# RoverWing-V1_3.net
KiCad netlist of a schematic drawn in EAGLE
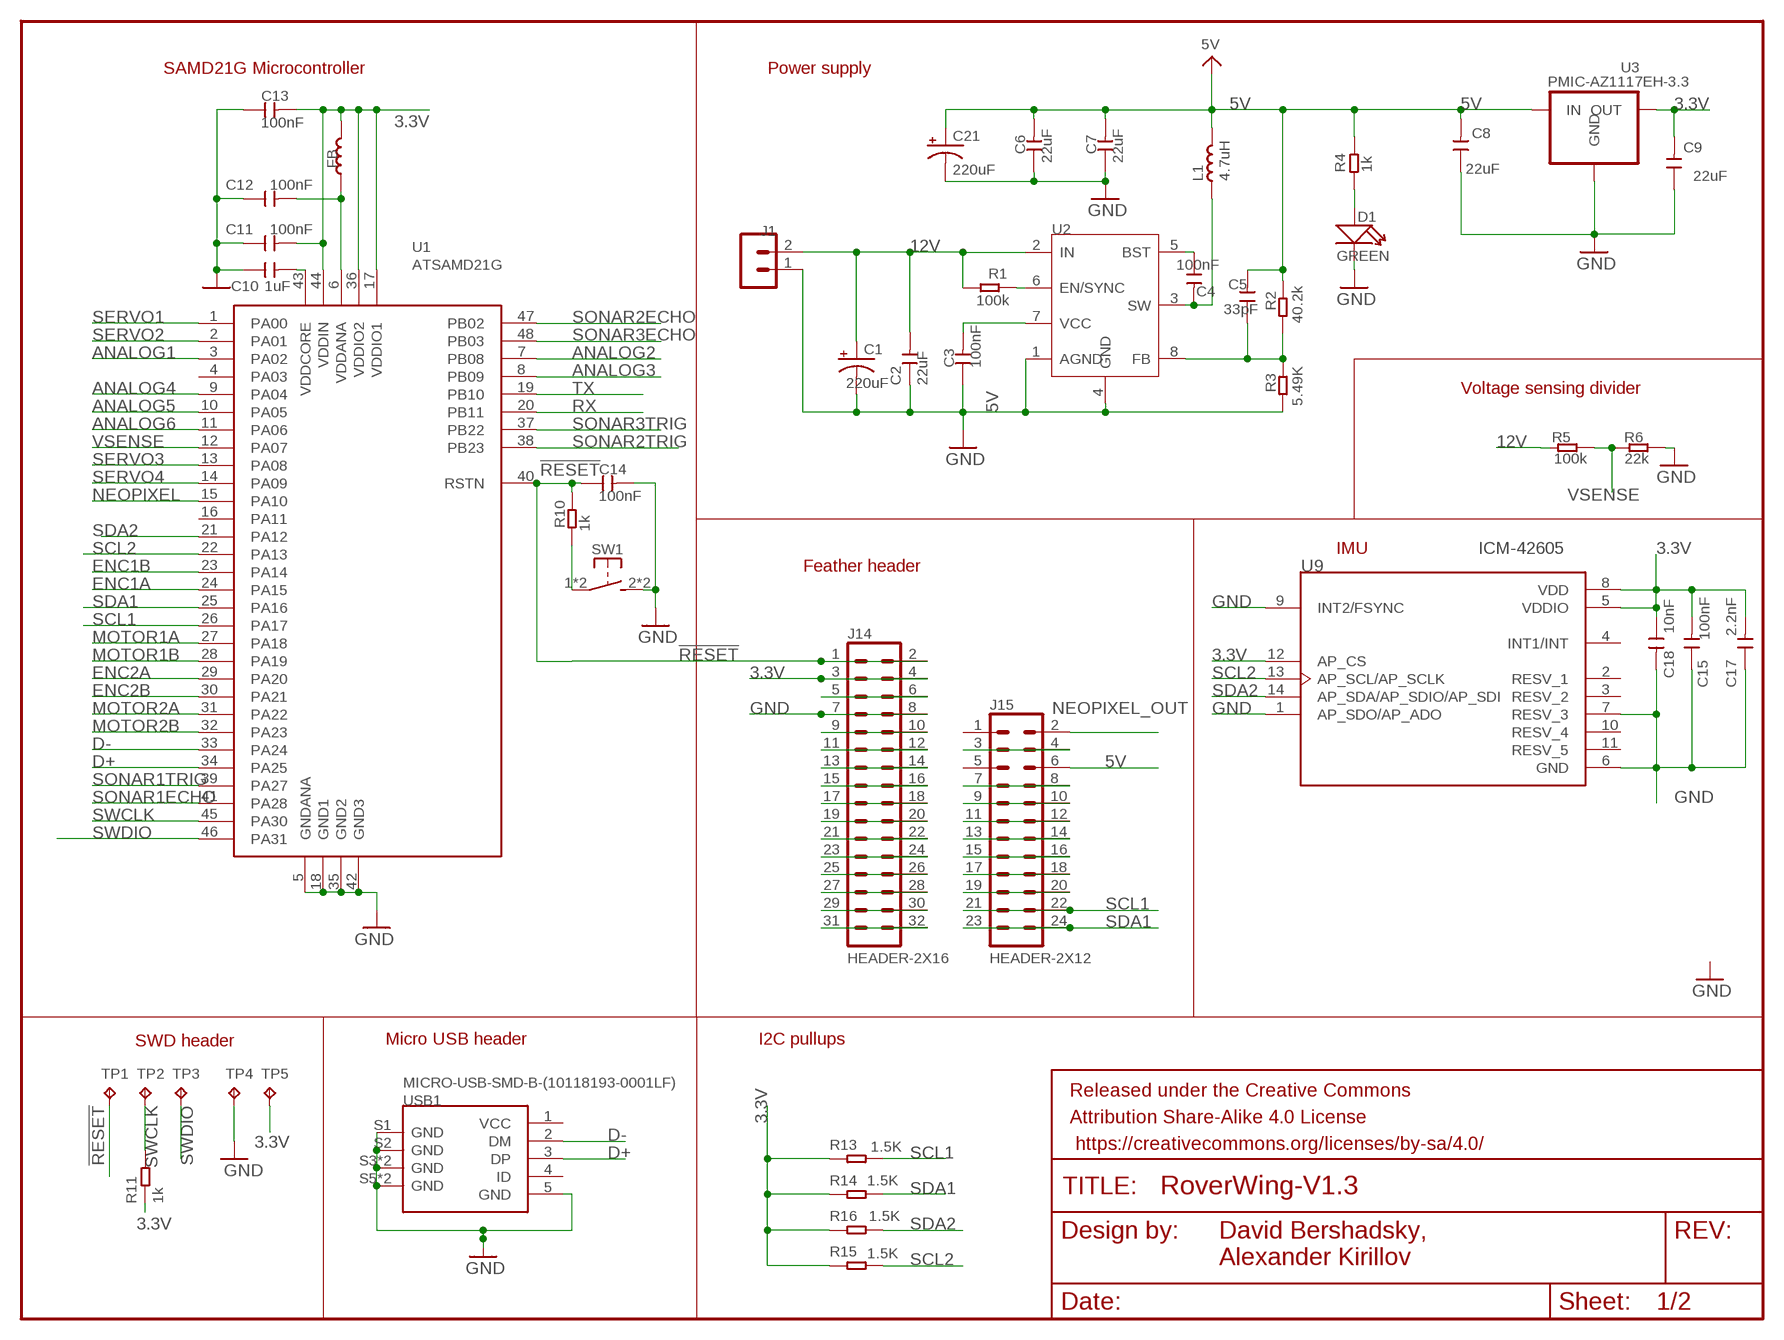
[diagram p0: schematic, sheet 1]
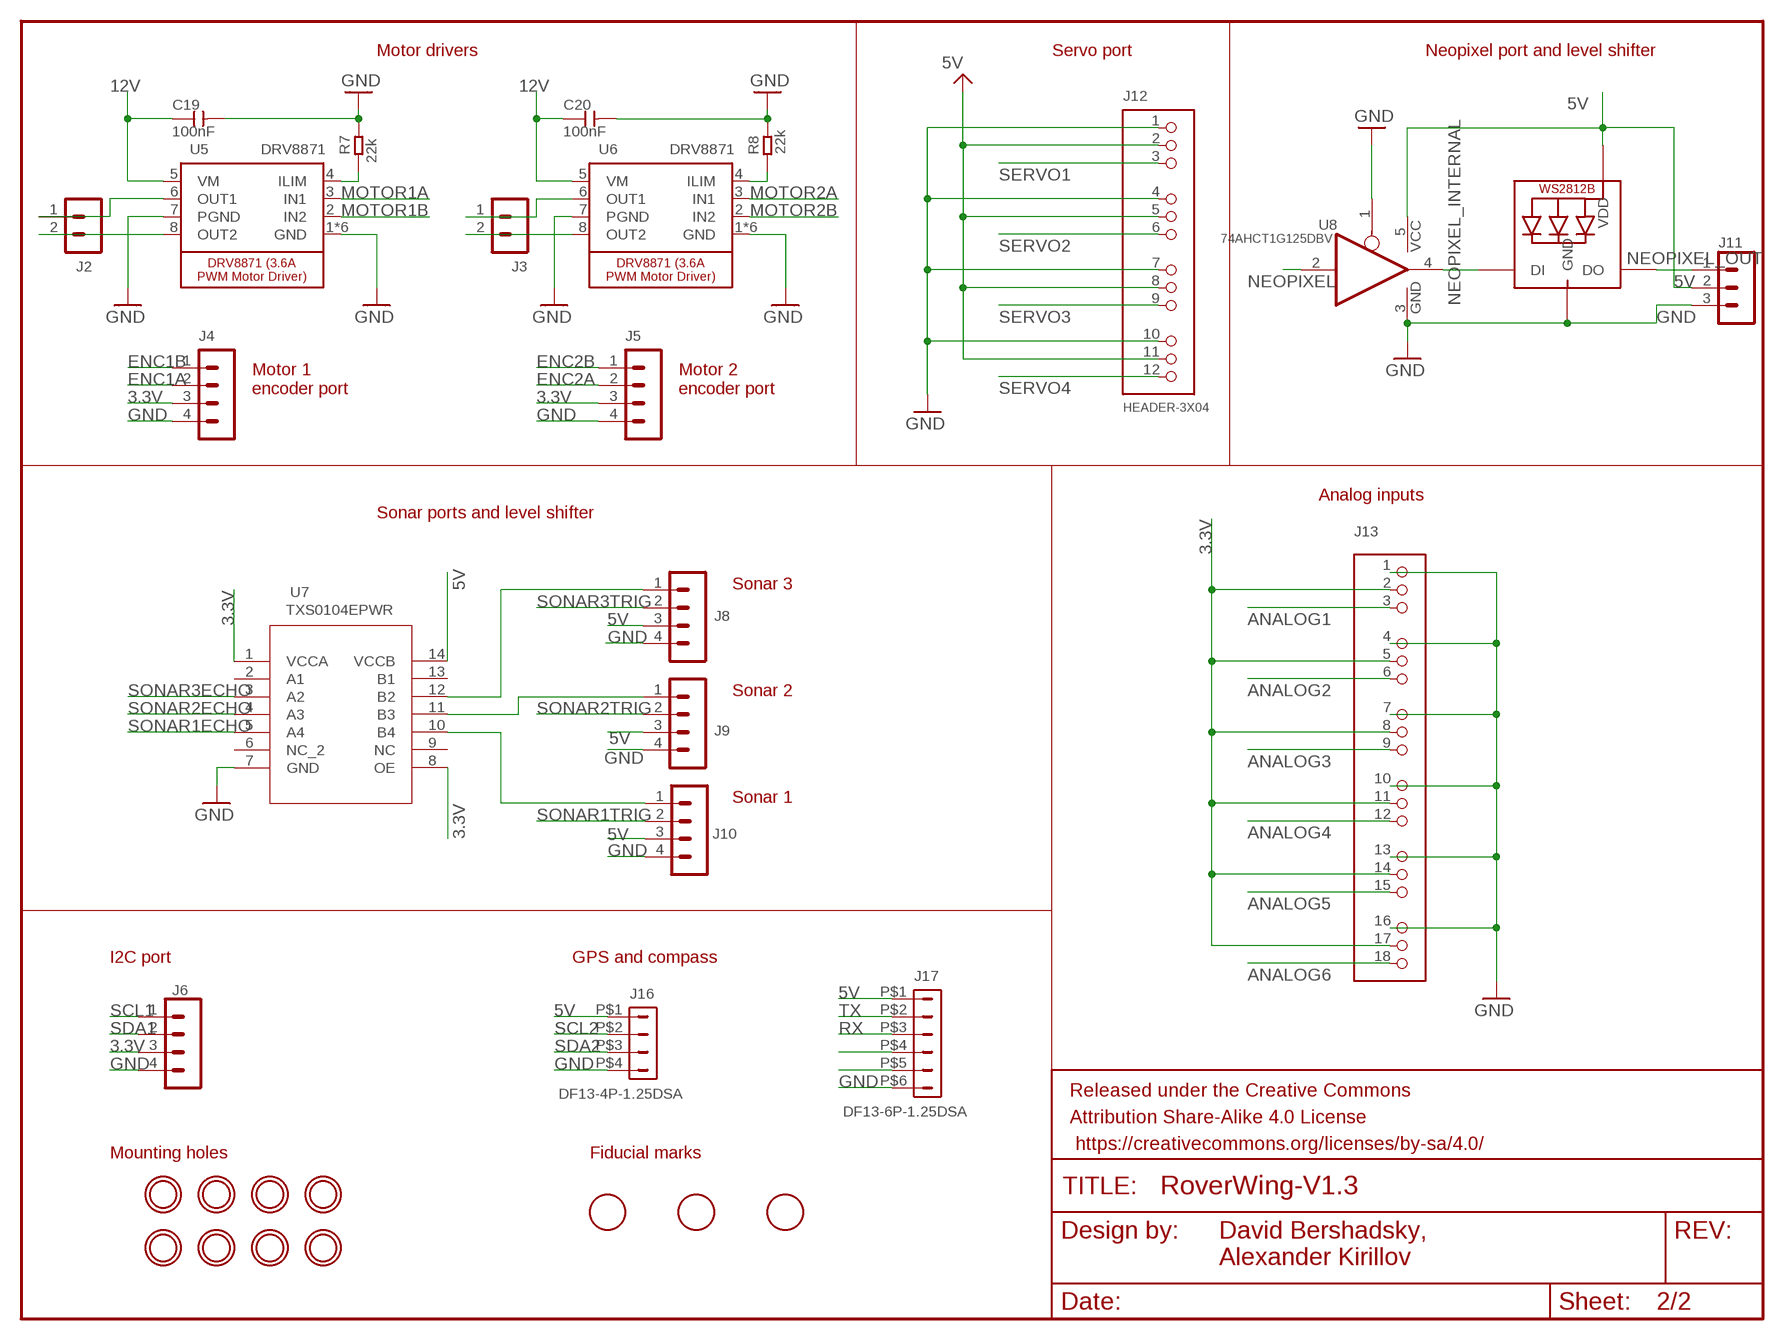
[diagram p1: schematic, sheet 2]

(export (version "E")
  (design (tool "Eeschema 10.0.6"))
  (components
    (comp (ref "C1")
      (value "220uF")
      (footprint "eagle-import:CAP-8X10.5")
      (libsource (lib "eagle-import") (part "CAP-POL-SMD-8X10.5"))
    )
    (comp (ref "C2")
      (value "22uF")
      (footprint "eagle-import:0805")
      (libsource (lib "eagle-import") (part "CAP-CERAMIC-SMD0805"))
    )
    (comp (ref "C3")
      (value "100nF")
      (footprint "eagle-import:0805")
      (libsource (lib "eagle-import") (part "CAP-CERAMIC-SMD0805"))
    )
    (comp (ref "C4")
      (value "100nF")
      (footprint "eagle-import:0805")
      (libsource (lib "eagle-import") (part "CAP-CERAMIC-SMD0805"))
    )
    (comp (ref "C5")
      (value "33pF")
      (footprint "eagle-import:0805")
      (libsource (lib "eagle-import") (part "CAP-CERAMIC-SMD0805"))
    )
    (comp (ref "C6")
      (value "22uF")
      (footprint "eagle-import:0805")
      (libsource (lib "eagle-import") (part "CAP-CERAMIC-SMD0805"))
    )
    (comp (ref "C7")
      (value "22uF")
      (footprint "eagle-import:0805")
      (libsource (lib "eagle-import") (part "CAP-CERAMIC-SMD0805"))
    )
    (comp (ref "C8")
      (value "22uF")
      (footprint "eagle-import:0805")
      (libsource (lib "eagle-import") (part "CAP-CERAMIC-SMD0805"))
    )
    (comp (ref "C9")
      (value "22uF")
      (footprint "eagle-import:0805")
      (libsource (lib "eagle-import") (part "CAP-CERAMIC-SMD0805"))
    )
    (comp (ref "C10")
      (value "1uF")
      (footprint "eagle-import:0805")
      (libsource (lib "eagle-import") (part "CAP-CERAMIC-SMD0805"))
    )
    (comp (ref "C11")
      (value "100nF")
      (footprint "eagle-import:0805")
      (libsource (lib "eagle-import") (part "CAP-CERAMIC-SMD0805"))
    )
    (comp (ref "C12")
      (value "100nF")
      (footprint "eagle-import:0805")
      (libsource (lib "eagle-import") (part "CAP-CERAMIC-SMD0805"))
    )
    (comp (ref "C13")
      (value "100nF")
      (footprint "eagle-import:0805")
      (libsource (lib "eagle-import") (part "CAP-CERAMIC-SMD0805"))
    )
    (comp (ref "C14")
      (value "100nF")
      (footprint "eagle-import:0805")
      (libsource (lib "eagle-import") (part "CAP-CERAMIC-SMD0805"))
    )
    (comp (ref "C15")
      (value "100nF")
      (footprint "eagle-import:0805")
      (libsource (lib "eagle-import") (part "CAP-CERAMIC-SMD0805"))
    )
    (comp (ref "C17")
      (value "2.2nF")
      (footprint "eagle-import:0805")
      (libsource (lib "eagle-import") (part "CAP-CERAMIC-SMD0805"))
    )
    (comp (ref "C18")
      (value "10nF")
      (footprint "eagle-import:0805")
      (libsource (lib "eagle-import") (part "CAP-CERAMIC-SMD0805"))
    )
    (comp (ref "C21")
      (value "220uF")
      (footprint "eagle-import:CAP-6.3X5.4")
      (fields (field (name "PARTNO") "CS1E470M-CRE54 "))
      (libsource (lib "eagle-import") (part "CAP-POL-SMD-6.3X5.4"))
    )
    (comp (ref "D1")
      (value "GREEN")
      (footprint "eagle-import:LED-0805")
      (libsource (lib "eagle-import") (part "SMD-LED-0805"))
    )
    (comp (ref "FB")
      (value "330R-1500MA")
      (footprint "eagle-import:0805")
      (fields (field (name "PARTNO") "BLM21PG331SN1D"))
      (libsource (lib "eagle-import") (part "SMD-FERRITE-BEAD-330R-1500MA(0805)"))
    )
    (comp (ref "FRAME2")
      (value "FRAME-LETTERNO_PACKAGE")
      (footprint "eagle-import:DUMMY")
      (libsource (lib "eagle-import") (part "FRAME-LETTERNO_PACKAGE"))
    )
    (comp (ref "J1")
      (value "HEADER-VH")
      (footprint "eagle-import:B2P-VH")
      (fields (field (name "PARTNO") "B2P-VH(LF)(SN)  "))
      (libsource (lib "eagle-import") (part "HEADER-VH"))
    )
    (comp (ref "J14")
      (value "HEADER-2X16")
      (footprint "eagle-import:2X16")
      (libsource (lib "eagle-import") (part "HEADER-2X16"))
    )
    (comp (ref "J15")
      (value "HEADER-2X12")
      (footprint "eagle-import:2X12")
      (libsource (lib "eagle-import") (part "HEADER-2X12"))
    )
    (comp (ref "L1")
      (value "4.7uH")
      (footprint "eagle-import:IND_TDK_7.1X6.5")
      (fields (field (name "MANUFACTURER") "TDK") (field (name "PARTNO") "SPM6530T-4R7M "))
      (libsource (lib "eagle-import") (part "IND-TDK-SPM6530T"))
    )
    (comp (ref "R1")
      (value "100k")
      (footprint "eagle-import:0805")
      (libsource (lib "eagle-import") (part "RES-SMD-0805"))
    )
    (comp (ref "R2")
      (value "40.2k")
      (footprint "eagle-import:0805")
      (libsource (lib "eagle-import") (part "RES-SMD-0805"))
    )
    (comp (ref "R3")
      (value "5.49K")
      (footprint "eagle-import:0805")
      (libsource (lib "eagle-import") (part "RES-SMD-0805"))
    )
    (comp (ref "R4")
      (value "1k")
      (footprint "eagle-import:0805")
      (libsource (lib "eagle-import") (part "RES-SMD-0805"))
    )
    (comp (ref "R5")
      (value "100k")
      (footprint "eagle-import:0805")
      (libsource (lib "eagle-import") (part "RES-SMD-0805"))
    )
    (comp (ref "R6")
      (value "22k")
      (footprint "eagle-import:0805")
      (libsource (lib "eagle-import") (part "RES-SMD-0805"))
    )
    (comp (ref "R10")
      (value "1k")
      (footprint "eagle-import:0805")
      (libsource (lib "eagle-import") (part "RES-SMD-0805"))
    )
    (comp (ref "R11")
      (value "1k")
      (footprint "eagle-import:0805")
      (libsource (lib "eagle-import") (part "RES-SMD-0805"))
    )
    (comp (ref "R13")
      (value "1.5K")
      (footprint "eagle-import:R0603")
      (fields (field (name "MPN") "RC0603FR-071K8L"))
      (libsource (lib "eagle-import") (part "SMD-RES-1.8K-1%-1/10W(0603)"))
    )
    (comp (ref "R14")
      (value "1.5K")
      (footprint "eagle-import:R0603")
      (fields (field (name "MPN") "RC0603FR-071K8L"))
      (libsource (lib "eagle-import") (part "SMD-RES-1.8K-1%-1/10W(0603)"))
    )
    (comp (ref "R15")
      (value "1.5K")
      (footprint "eagle-import:R0603")
      (fields (field (name "MPN") "RC0603FR-071K8L"))
      (libsource (lib "eagle-import") (part "SMD-RES-1.8K-1%-1/10W(0603)"))
    )
    (comp (ref "R16")
      (value "1.5K")
      (footprint "eagle-import:R0603")
      (fields (field (name "MPN") "RC0603FR-071K8L"))
      (libsource (lib "eagle-import") (part "SMD-RES-1.8K-1%-1/10W(0603)"))
    )
    (comp (ref "SW1")
      (value "SW-TACTILE-4.5X4.5_SMD")
      (footprint "eagle-import:TL3305")
      (fields (field (name "MANUFACTURER") "BRIGHT") (field (name "PARTNO") "TSA453G38-250 "))
      (libsource (lib "eagle-import") (part "SW-TACTILE-4.5X4.5_SMD"))
    )
    (comp (ref "TP1")
      (value "TPTP15R")
      (footprint "eagle-import:TP15R")
      (libsource (lib "eagle-import") (part "TPTP15R"))
    )
    (comp (ref "TP2")
      (value "TPTP15R")
      (footprint "eagle-import:TP15R")
      (libsource (lib "eagle-import") (part "TPTP15R"))
    )
    (comp (ref "TP3")
      (value "TPTP15R")
      (footprint "eagle-import:TP15R")
      (libsource (lib "eagle-import") (part "TPTP15R"))
    )
    (comp (ref "TP4")
      (value "TPTP15R")
      (footprint "eagle-import:TP15R")
      (libsource (lib "eagle-import") (part "TPTP15R"))
    )
    (comp (ref "TP5")
      (value "TPTP15R")
      (footprint "eagle-import:TP15R")
      (libsource (lib "eagle-import") (part "TPTP15R"))
    )
    (comp (ref "U1")
      (value "ATSAMD21G")
      (footprint "eagle-import:TQFP-48-EDITED")
      (fields (field (name "MANUFACTURER") "Microchip Technology") (field (name "PARTNO") "ATSAMD21G18A-AU"))
      (libsource (lib "eagle-import") (part "ATSAMD21G"))
    )
    (comp (ref "U2")
      (value "MP2225")
      (footprint "eagle-import:SOT-23-8")
      (fields (field (name "MANUFACTURER") "Monolithic Power Systems") (field (name "PARTNO") "MP2225GJ"))
      (libsource (lib "eagle-import") (part "PMIC-MP2225"))
    )
    (comp (ref "U3")
      (value "PMIC-AZ1117EH-3.3")
      (footprint "eagle-import:SOT223")
      (fields (field (name "PARTNO") "AZ1117EH-3.3TRG1"))
      (libsource (lib "eagle-import") (part "PMIC-AZ1117EH-3.3"))
    )
    (comp (ref "U9")
      (value "ICM-42605")
      (footprint "eagle-import:PQFN50P300X250X97-14N")
      (fields (field (name "DIGI-KEY_PART_NUMBER") "1428-1152-1-ND") (field (name "MF") "TDK InvenSense"))
      (libsource (lib "eagle-import") (part "ICM-42605"))
    )
    (comp (ref "USB1")
      (value "MICRO-USB-SMD-B-(10118193-0001LF)")
      (footprint "eagle-import:MICRO-USB5+6P-SMD-0.65-B")
      (fields (field (name "MANUFACTURER") "Amphenol ICC") (field (name "PARTNO") "10118193-0001LF"))
      (libsource (lib "eagle-import") (part "MICRO-USB-SMD-B-(10118193-0001LF)"))
    )
    (comp (ref "C19")
      (value "100nF")
      (footprint "eagle-import:0805")
      (libsource (lib "eagle-import") (part "CAP-CERAMIC-SMD0805"))
    )
    (comp (ref "C20")
      (value "100nF")
      (footprint "eagle-import:0805")
      (libsource (lib "eagle-import") (part "CAP-CERAMIC-SMD0805"))
    )
    (comp (ref "D2")
      (value "WS2812B3535")
      (footprint "eagle-import:LED3535")
      (fields (field (name "MANUFACTURER") "Worldsemi") (field (name "PARTNO") "WS2812B-3535 "))
      (libsource (lib "eagle-import") (part "WS2812B3535"))
    )
    (comp (ref "FRAME1")
      (value "FRAME-LETTERNO_PACKAGE")
      (footprint "eagle-import:DUMMY")
      (libsource (lib "eagle-import") (part "FRAME-LETTERNO_PACKAGE"))
    )
    (comp (ref "J2")
      (value "HEADER-VH")
      (footprint "eagle-import:B2P-VH")
      (fields (field (name "PARTNO") "B2P-VH(LF)(SN)  "))
      (libsource (lib "eagle-import") (part "HEADER-VH"))
    )
    (comp (ref "J3")
      (value "HEADER-VH")
      (footprint "eagle-import:B2P-VH")
      (fields (field (name "PARTNO") "B2P-VH(LF)(SN)  "))
      (libsource (lib "eagle-import") (part "HEADER-VH"))
    )
    (comp (ref "J4")
      (value "HEADER-PH-4P")
      (footprint "eagle-import:B4B-PH-K")
      (fields (field (name "PARTNO") "B4B-PH-K-S(LF)(SN)"))
      (libsource (lib "eagle-import") (part "HEADER-PH-4P"))
    )
    (comp (ref "J5")
      (value "HEADER-PH-4P")
      (footprint "eagle-import:B4B-PH-K")
      (fields (field (name "PARTNO") "B4B-PH-K-S(LF)(SN)"))
      (libsource (lib "eagle-import") (part "HEADER-PH-4P"))
    )
    (comp (ref "J6")
      (value "HEADER-PH-4P")
      (footprint "eagle-import:B4B-PH-K")
      (fields (field (name "PARTNO") "B4B-PH-K-S(LF)(SN)"))
      (libsource (lib "eagle-import") (part "HEADER-PH-4P"))
    )
    (comp (ref "J8")
      (value "HEADER-PH-4P")
      (footprint "eagle-import:B4B-PH-K")
      (fields (field (name "PARTNO") "B4B-PH-K-S(LF)(SN)"))
      (libsource (lib "eagle-import") (part "HEADER-PH-4P"))
    )
    (comp (ref "J9")
      (value "HEADER-PH-4P")
      (footprint "eagle-import:B4B-PH-K")
      (fields (field (name "PARTNO") "B4B-PH-K-S(LF)(SN)"))
      (libsource (lib "eagle-import") (part "HEADER-PH-4P"))
    )
    (comp (ref "J10")
      (value "HEADER-PH-4P")
      (footprint "eagle-import:B4B-PH-K")
      (fields (field (name "PARTNO") "B4B-PH-K-S(LF)(SN)"))
      (libsource (lib "eagle-import") (part "HEADER-PH-4P"))
    )
    (comp (ref "J11")
      (value "HEADER-PH-3P")
      (footprint "eagle-import:B3B-PH-K")
      (fields (field (name "PARTNO") "B3B-PH-K-S(LF)(SN)"))
      (libsource (lib "eagle-import") (part "HEADER-PH-3P"))
    )
    (comp (ref "J12")
      (value "HEADER-3X04")
      (footprint "eagle-import:3X04")
      (libsource (lib "eagle-import") (part "HEADER-3X04"))
    )
    (comp (ref "J13")
      (value "HEADER-3X06\"")
      (footprint "eagle-import:3X06")
      (libsource (lib "eagle-import") (part "HEADER-3X06{dblquote}"))
    )
    (comp (ref "J16")
      (value "DF13-4P-1.25DSA")
      (footprint "eagle-import:DF13-4P-1.25DSA")
      (libsource (lib "eagle-import") (part "DF13-4P-1.25DSA"))
    )
    (comp (ref "J17")
      (value "DF13-6P-1.25DSA")
      (footprint "eagle-import:DF13-6P-1.25DSA")
      (libsource (lib "eagle-import") (part "DF13-6P-1.25DSA"))
    )
    (comp (ref "R7")
      (value "22k")
      (footprint "eagle-import:0805")
      (libsource (lib "eagle-import") (part "RES-SMD-0805"))
    )
    (comp (ref "R8")
      (value "22k")
      (footprint "eagle-import:0805")
      (libsource (lib "eagle-import") (part "RES-SMD-0805"))
    )
    (comp (ref "U$3")
      (value "MOUNTINGHOLE3.0_NPH")
      (footprint "eagle-import:MOUNTINGHOLE_3.0_NPH")
      (libsource (lib "eagle-import") (part "MOUNTINGHOLE3.0_NPH"))
    )
    (comp (ref "U$4")
      (value "MOUNTINGHOLE3.0_NPH")
      (footprint "eagle-import:MOUNTINGHOLE_3.0_NPH")
      (libsource (lib "eagle-import") (part "MOUNTINGHOLE3.0_NPH"))
    )
    (comp (ref "U$11")
      (value "FIDUCIAL")
      (footprint "eagle-import:FIDUCIAL_1MM")
      (libsource (lib "eagle-import") (part "FIDUCIAL"))
    )
    (comp (ref "U$13")
      (value "FIDUCIAL")
      (footprint "eagle-import:FIDUCIAL_1MM")
      (libsource (lib "eagle-import") (part "FIDUCIAL"))
    )
    (comp (ref "U$14")
      (value "MOUNTINGHOLE3.0_NPH")
      (footprint "eagle-import:MOUNTINGHOLE_3.0_NPH")
      (libsource (lib "eagle-import") (part "MOUNTINGHOLE3.0_NPH"))
    )
    (comp (ref "U$15")
      (value "MOUNTINGHOLE3.0_NPH")
      (footprint "eagle-import:MOUNTINGHOLE_3.0_NPH")
      (libsource (lib "eagle-import") (part "MOUNTINGHOLE3.0_NPH"))
    )
    (comp (ref "U$17")
      (value "FIDUCIAL")
      (footprint "eagle-import:FIDUCIAL_1MM")
      (libsource (lib "eagle-import") (part "FIDUCIAL"))
    )
    (comp (ref "U$24")
      (value "MOUNTINGHOLE3.0_NPH")
      (footprint "eagle-import:MOUNTINGHOLE_3.0_NPH")
      (libsource (lib "eagle-import") (part "MOUNTINGHOLE3.0_NPH"))
    )
    (comp (ref "U$25")
      (value "MOUNTINGHOLE3.0_NPH")
      (footprint "eagle-import:MOUNTINGHOLE_3.0_NPH")
      (libsource (lib "eagle-import") (part "MOUNTINGHOLE3.0_NPH"))
    )
    (comp (ref "U$26")
      (value "MOUNTINGHOLE3.0_NPH")
      (footprint "eagle-import:MOUNTINGHOLE_3.0_NPH")
      (libsource (lib "eagle-import") (part "MOUNTINGHOLE3.0_NPH"))
    )
    (comp (ref "U$27")
      (value "MOUNTINGHOLE3.0_NPH")
      (footprint "eagle-import:MOUNTINGHOLE_3.0_NPH")
      (libsource (lib "eagle-import") (part "MOUNTINGHOLE3.0_NPH"))
    )
    (comp (ref "U5")
      (value "DRV8871")
      (footprint "eagle-import:HSOP8")
      (fields (field (name "MANUFACTURER") "TEXAS INSTRUMENTS") (field (name "PARTNO") "DRV8871DDAR"))
      (libsource (lib "eagle-import") (part "DRV8871"))
    )
    (comp (ref "U6")
      (value "DRV8871")
      (footprint "eagle-import:HSOP8")
      (fields (field (name "MANUFACTURER") "TEXAS INSTRUMENTS") (field (name "PARTNO") "DRV8871DDAR"))
      (libsource (lib "eagle-import") (part "DRV8871"))
    )
    (comp (ref "U7")
      (value "TXS0104EPWR")
      (footprint "eagle-import:PW14")
      (fields (field (name "MANUFACTURER") "Texas Instruments"))
      (libsource (lib "eagle-import") (part "TXS0104EPWR"))
    )
    (comp (ref "U8")
      (value "74AHCT1G125DBV")
      (footprint "eagle-import:SOT23-5")
      (fields (field (name "PARTNO") "SN74AHCT1G125DBVR"))
      (libsource (lib "eagle-import") (part "741G125DBVAHCT"))
    )
  )
  (nets
    (net (code "1") (name "3.3V") (class "Default")
      (node (ref "C11") (pin "2") (pinfunction "2_2") (pintype "passive"))
      (node (ref "C13") (pin "2") (pinfunction "2_2") (pintype "passive"))
      (node (ref "C15") (pin "2") (pinfunction "2_2") (pintype "passive"))
      (node (ref "C17") (pin "2") (pinfunction "2_2") (pintype "passive"))
      (node (ref "C18") (pin "1") (pinfunction "1_1") (pintype "passive"))
      (node (ref "C9") (pin "2") (pinfunction "2_2") (pintype "passive"))
      (node (ref "FB") (pin "2") (pinfunction "2_2") (pintype "passive"))
      (node (ref "J13") (pin "11") (pinfunction "11_11") (pintype "passive"))
      (node (ref "J13") (pin "14") (pinfunction "14_14") (pintype "passive"))
      (node (ref "J13") (pin "17") (pinfunction "17_17") (pintype "passive"))
      (node (ref "J13") (pin "2") (pinfunction "2_2") (pintype "passive"))
      (node (ref "J13") (pin "5") (pinfunction "5_5") (pintype "passive"))
      (node (ref "J13") (pin "8") (pinfunction "8_8") (pintype "passive"))
      (node (ref "J14") (pin "3") (pinfunction "3_3") (pintype "passive"))
      (node (ref "J14") (pin "4") (pinfunction "4_4") (pintype "passive"))
      (node (ref "J4") (pin "3") (pinfunction "3_3") (pintype "passive"))
      (node (ref "J5") (pin "3") (pinfunction "3_3") (pintype "passive"))
      (node (ref "J6") (pin "3") (pinfunction "3_3") (pintype "passive"))
      (node (ref "R11") (pin "1") (pinfunction "1_1") (pintype "passive"))
      (node (ref "R13") (pin "1") (pinfunction "1_1") (pintype "passive"))
      (node (ref "R14") (pin "1") (pinfunction "1_1") (pintype "passive"))
      (node (ref "R15") (pin "1") (pinfunction "1_1") (pintype "passive"))
      (node (ref "R16") (pin "1") (pinfunction "1_1") (pintype "passive"))
      (node (ref "TP5") (pin "TP") (pinfunction "TP_TP") (pintype "input"))
      (node (ref "U1") (pin "17") (pinfunction "VDDIO1_17") (pintype "power_in"))
      (node (ref "U1") (pin "36") (pinfunction "VDDIO2_36") (pintype "power_in"))
      (node (ref "U1") (pin "44") (pinfunction "VDDIN_44") (pintype "power_in"))
      (node (ref "U3") (pin "2") (pinfunction "OUT_2") (pintype "output"))
      (node (ref "U3") (pin "4") (pinfunction "OUT_4") (pintype "output"))
      (node (ref "U7") (pin "1") (pinfunction "VCCA_1") (pintype "power_in"))
      (node (ref "U7") (pin "8") (pinfunction "OE_8") (pintype "output"))
      (node (ref "U9") (pin "12") (pinfunction "AP_CS_12") (pintype "input"))
      (node (ref "U9") (pin "5") (pinfunction "VDDIO_5") (pintype "power_in"))
      (node (ref "U9") (pin "8") (pinfunction "VDD_8") (pintype "power_in"))
    )
    (net (code "2") (name "5V") (class "Default")
      (node (ref "C21") (pin "+") (pinfunction "+_+") (pintype "passive"))
      (node (ref "C5") (pin "2") (pinfunction "2_2") (pintype "passive"))
      (node (ref "C6") (pin "2") (pinfunction "2_2") (pintype "passive"))
      (node (ref "C7") (pin "2") (pinfunction "2_2") (pintype "passive"))
      (node (ref "C8") (pin "2") (pinfunction "2_2") (pintype "passive"))
      (node (ref "D2") (pin "3") (pinfunction "VDD_3") (pintype "power_in"))
      (node (ref "J10") (pin "3") (pinfunction "3_3") (pintype "passive"))
      (node (ref "J11") (pin "2") (pinfunction "2_2") (pintype "passive"))
      (node (ref "J12") (pin "11") (pinfunction "11_11") (pintype "passive"))
      (node (ref "J12") (pin "2") (pinfunction "2_2") (pintype "passive"))
      (node (ref "J12") (pin "5") (pinfunction "5_5") (pintype "passive"))
      (node (ref "J12") (pin "8") (pinfunction "8_8") (pintype "passive"))
      (node (ref "J15") (pin "6") (pinfunction "6_6") (pintype "passive"))
      (node (ref "J16") (pin "P$1") (pinfunction "1_P$1") (pintype "passive"))
      (node (ref "J17") (pin "P$1") (pinfunction "1_P$1") (pintype "passive"))
      (node (ref "J8") (pin "3") (pinfunction "3_3") (pintype "passive"))
      (node (ref "J9") (pin "3") (pinfunction "3_3") (pintype "passive"))
      (node (ref "L1") (pin "2") (pinfunction "2_2") (pintype "passive"))
      (node (ref "R2") (pin "1") (pinfunction "1_1") (pintype "passive"))
      (node (ref "R4") (pin "2") (pinfunction "2_2") (pintype "passive"))
      (node (ref "U3") (pin "3") (pinfunction "IN_3") (pintype "input"))
      (node (ref "U7") (pin "14") (pinfunction "VCCB_14") (pintype "power_in"))
      (node (ref "U8") (pin "5") (pinfunction "VCC_5") (pintype "power_in"))
    )
    (net (code "3") (name "12V") (class "Default")
      (node (ref "C1") (pin "+") (pinfunction "+_+") (pintype "passive"))
      (node (ref "C19") (pin "1") (pinfunction "1_1") (pintype "passive"))
      (node (ref "C2") (pin "2") (pinfunction "2_2") (pintype "passive"))
      (node (ref "C20") (pin "1") (pinfunction "1_1") (pintype "passive"))
      (node (ref "J1") (pin "2") (pinfunction "2_2") (pintype "passive"))
      (node (ref "R1") (pin "2") (pinfunction "2_2") (pintype "passive"))
      (node (ref "R5") (pin "2") (pinfunction "2_2") (pintype "passive"))
      (node (ref "U2") (pin "2") (pinfunction "IN_2") (pintype "bidirectional"))
      (node (ref "U5") (pin "5") (pinfunction "VM_5") (pintype "power_in"))
      (node (ref "U6") (pin "5") (pinfunction "VM_5") (pintype "power_in"))
    )
    (net (code "4") (name "ANALOG1") (class "Default")
      (node (ref "J13") (pin "3") (pinfunction "3_3") (pintype "passive"))
      (node (ref "U1") (pin "3") (pinfunction "PA02_3") (pintype "bidirectional"))
    )
    (net (code "5") (name "ANALOG2") (class "Default")
      (node (ref "J13") (pin "6") (pinfunction "6_6") (pintype "passive"))
      (node (ref "U1") (pin "7") (pinfunction "PB08_7") (pintype "bidirectional"))
    )
    (net (code "6") (name "ANALOG3") (class "Default")
      (node (ref "J13") (pin "9") (pinfunction "9_9") (pintype "passive"))
      (node (ref "U1") (pin "8") (pinfunction "PB09_8") (pintype "bidirectional"))
    )
    (net (code "7") (name "ANALOG4") (class "Default")
      (node (ref "J13") (pin "12") (pinfunction "12_12") (pintype "passive"))
      (node (ref "U1") (pin "9") (pinfunction "PA04_9") (pintype "bidirectional"))
    )
    (net (code "8") (name "ANALOG5") (class "Default")
      (node (ref "J13") (pin "15") (pinfunction "15_15") (pintype "passive"))
      (node (ref "U1") (pin "10") (pinfunction "PA05_10") (pintype "bidirectional"))
    )
    (net (code "9") (name "ANALOG6") (class "Default")
      (node (ref "J13") (pin "18") (pinfunction "18_18") (pintype "passive"))
      (node (ref "U1") (pin "11") (pinfunction "PA06_11") (pintype "bidirectional"))
    )
    (net (code "10") (name "D+") (class "Default")
      (node (ref "U1") (pin "34") (pinfunction "PA25_34") (pintype "bidirectional"))
      (node (ref "USB1") (pin "3") (pinfunction "DP_3") (pintype "bidirectional"))
    )
    (net (code "11") (name "D-") (class "Default")
      (node (ref "U1") (pin "33") (pinfunction "PA24_33") (pintype "bidirectional"))
      (node (ref "USB1") (pin "2") (pinfunction "DM_2") (pintype "bidirectional"))
    )
    (net (code "12") (name "ENC1A") (class "Default")
      (node (ref "J4") (pin "2") (pinfunction "2_2") (pintype "passive"))
      (node (ref "U1") (pin "24") (pinfunction "PA15_24") (pintype "bidirectional"))
    )
    (net (code "13") (name "ENC1B") (class "Default")
      (node (ref "J4") (pin "1") (pinfunction "1_1") (pintype "passive"))
      (node (ref "U1") (pin "23") (pinfunction "PA14_23") (pintype "bidirectional"))
    )
    (net (code "14") (name "ENC2A") (class "Default")
      (node (ref "J5") (pin "2") (pinfunction "2_2") (pintype "passive"))
      (node (ref "U1") (pin "29") (pinfunction "PA20_29") (pintype "bidirectional"))
    )
    (net (code "15") (name "ENC2B") (class "Default")
      (node (ref "J5") (pin "1") (pinfunction "1_1") (pintype "passive"))
      (node (ref "U1") (pin "30") (pinfunction "PA21_30") (pintype "bidirectional"))
    )
    (net (code "16") (name "GND") (class "Default")
      (node (ref "C1") (pin "-") (pinfunction "-_-") (pintype "passive"))
      (node (ref "C10") (pin "1") (pinfunction "1_1") (pintype "passive"))
      (node (ref "C11") (pin "1") (pinfunction "1_1") (pintype "passive"))
      (node (ref "C12") (pin "1") (pinfunction "1_1") (pintype "passive"))
      (node (ref "C13") (pin "1") (pinfunction "1_1") (pintype "passive"))
      (node (ref "C14") (pin "2") (pinfunction "2_2") (pintype "passive"))
      (node (ref "C15") (pin "1") (pinfunction "1_1") (pintype "passive"))
      (node (ref "C17") (pin "1") (pinfunction "1_1") (pintype "passive"))
      (node (ref "C18") (pin "2") (pinfunction "2_2") (pintype "passive"))
      (node (ref "C19") (pin "2") (pinfunction "2_2") (pintype "passive"))
      (node (ref "C2") (pin "1") (pinfunction "1_1") (pintype "passive"))
      (node (ref "C20") (pin "2") (pinfunction "2_2") (pintype "passive"))
      (node (ref "C21") (pin "-") (pinfunction "-_-") (pintype "passive"))
      (node (ref "C3") (pin "1") (pinfunction "1_1") (pintype "passive"))
      (node (ref "C6") (pin "1") (pinfunction "1_1") (pintype "passive"))
      (node (ref "C7") (pin "1") (pinfunction "1_1") (pintype "passive"))
      (node (ref "C8") (pin "1") (pinfunction "1_1") (pintype "passive"))
      (node (ref "C9") (pin "1") (pinfunction "1_1") (pintype "passive"))
      (node (ref "D1") (pin "-") (pinfunction "-_-") (pintype "passive"))
      (node (ref "D2") (pin "1") (pinfunction "GND_1") (pintype "power_in"))
      (node (ref "J1") (pin "1") (pinfunction "1_1") (pintype "passive"))
      (node (ref "J10") (pin "4") (pinfunction "4_4") (pintype "passive"))
      (node (ref "J11") (pin "3") (pinfunction "3_3") (pintype "passive"))
      (node (ref "J12") (pin "1") (pinfunction "1_1") (pintype "passive"))
      (node (ref "J12") (pin "10") (pinfunction "10_10") (pintype "passive"))
      (node (ref "J12") (pin "4") (pinfunction "4_4") (pintype "passive"))
      (node (ref "J12") (pin "7") (pinfunction "7_7") (pintype "passive"))
      (node (ref "J13") (pin "1") (pinfunction "1_1") (pintype "passive"))
      (node (ref "J13") (pin "10") (pinfunction "10_10") (pintype "passive"))
      (node (ref "J13") (pin "13") (pinfunction "13_13") (pintype "passive"))
      (node (ref "J13") (pin "16") (pinfunction "16_16") (pintype "passive"))
      (node (ref "J13") (pin "4") (pinfunction "4_4") (pintype "passive"))
      (node (ref "J13") (pin "7") (pinfunction "7_7") (pintype "passive"))
      (node (ref "J14") (pin "7") (pinfunction "7_7") (pintype "passive"))
      (node (ref "J14") (pin "8") (pinfunction "8_8") (pintype "passive"))
      (node (ref "J16") (pin "P$4") (pinfunction "4_P$4") (pintype "passive"))
      (node (ref "J17") (pin "P$6") (pinfunction "6_P$6") (pintype "passive"))
      (node (ref "J4") (pin "4") (pinfunction "4_4") (pintype "passive"))
      (node (ref "J5") (pin "4") (pinfunction "4_4") (pintype "passive"))
      (node (ref "J6") (pin "4") (pinfunction "4_4") (pintype "passive"))
      (node (ref "J8") (pin "4") (pinfunction "4_4") (pintype "passive"))
      (node (ref "J9") (pin "4") (pinfunction "4_4") (pintype "passive"))
      (node (ref "R3") (pin "2") (pinfunction "2_2") (pintype "passive"))
      (node (ref "R6") (pin "2") (pinfunction "2_2") (pintype "passive"))
      (node (ref "R7") (pin "2") (pinfunction "2_2") (pintype "passive"))
      (node (ref "R8") (pin "2") (pinfunction "2_2") (pintype "passive"))
      (node (ref "SW1") (pin "2") (pinfunction "S1_2") (pintype "passive"))
      (node (ref "SW1") (pin "3") (pinfunction "S1_3") (pintype "passive"))
      (node (ref "TP4") (pin "TP") (pinfunction "TP_TP") (pintype "input"))
      (node (ref "U1") (pin "18") (pinfunction "GND1_18") (pintype "power_in"))
      (node (ref "U1") (pin "35") (pinfunction "GND2_35") (pintype "power_in"))
      (node (ref "U1") (pin "42") (pinfunction "GND3_42") (pintype "power_in"))
      (node (ref "U1") (pin "5") (pinfunction "GNDANA_5") (pintype "power_in"))
      (node (ref "U2") (pin "1") (pinfunction "AGND_1") (pintype "bidirectional"))
      (node (ref "U2") (pin "4") (pinfunction "GND_4") (pintype "bidirectional"))
      (node (ref "U3") (pin "1") (pinfunction "GND_1") (pintype "power_in"))
      (node (ref "U5") (pin "1") (pinfunction "GND_1") (pintype "power_in"))
      (node (ref "U5") (pin "7") (pinfunction "PGND_7") (pintype "power_in"))
      (node (ref "U5") (pin "GND") (pinfunction "GND_GND") (pintype "power_in"))
      (node (ref "U5") (pin "P$1") (pinfunction "GND_P$1") (pintype "power_in"))
      (node (ref "U5") (pin "P$2") (pinfunction "GND_P$2") (pintype "power_in"))
      (node (ref "U5") (pin "P$3") (pinfunction "GND_P$3") (pintype "power_in"))
      (node (ref "U5") (pin "P$4") (pinfunction "GND_P$4") (pintype "power_in"))
      (node (ref "U6") (pin "1") (pinfunction "GND_1") (pintype "power_in"))
      (node (ref "U6") (pin "7") (pinfunction "PGND_7") (pintype "power_in"))
      (node (ref "U6") (pin "GND") (pinfunction "GND_GND") (pintype "power_in"))
      (node (ref "U6") (pin "P$1") (pinfunction "GND_P$1") (pintype "power_in"))
      (node (ref "U6") (pin "P$2") (pinfunction "GND_P$2") (pintype "power_in"))
      (node (ref "U6") (pin "P$3") (pinfunction "GND_P$3") (pintype "power_in"))
      (node (ref "U6") (pin "P$4") (pinfunction "GND_P$4") (pintype "power_in"))
      (node (ref "U7") (pin "7") (pinfunction "GND_7") (pintype "power_in"))
      (node (ref "U8") (pin "1") (pinfunction "OE_1") (pintype "input"))
      (node (ref "U8") (pin "3") (pinfunction "GND_3") (pintype "power_in"))
      (node (ref "U9") (pin "1") (pinfunction "AP_SDO/AP_ADO_1") (pintype "output"))
      (node (ref "U9") (pin "6") (pinfunction "GND_6") (pintype "power_in"))
      (node (ref "U9") (pin "7") (pinfunction "RESV_3_7") (pintype "bidirectional"))
      (node (ref "U9") (pin "9") (pinfunction "INT2/FSYNC_9") (pintype "bidirectional"))
      (node (ref "USB1") (pin "5") (pinfunction "GND_5") (pintype "bidirectional"))
      (node (ref "USB1") (pin "S1") (pinfunction "GND_S1") (pintype "bidirectional"))
      (node (ref "USB1") (pin "S2") (pinfunction "GND_S2") (pintype "bidirectional"))
      (node (ref "USB1") (pin "S3") (pinfunction "GND_S3") (pintype "bidirectional"))
      (node (ref "USB1") (pin "S4") (pinfunction "GND_S4") (pintype "bidirectional"))
      (node (ref "USB1") (pin "S5") (pinfunction "GND_S5") (pintype "bidirectional"))
      (node (ref "USB1") (pin "S6") (pinfunction "GND_S6") (pintype "bidirectional"))
    )
    (net (code "17") (name "MOTOR1A") (class "Default")
      (node (ref "U1") (pin "27") (pinfunction "PA18_27") (pintype "bidirectional"))
      (node (ref "U5") (pin "3") (pinfunction "IN1_3") (pintype "input"))
    )
    (net (code "18") (name "MOTOR1B") (class "Default")
      (node (ref "U1") (pin "28") (pinfunction "PA19_28") (pintype "bidirectional"))
      (node (ref "U5") (pin "2") (pinfunction "IN2_2") (pintype "input"))
    )
    (net (code "19") (name "MOTOR2A") (class "Default")
      (node (ref "U1") (pin "31") (pinfunction "PA22_31") (pintype "bidirectional"))
      (node (ref "U6") (pin "3") (pinfunction "IN1_3") (pintype "input"))
    )
    (net (code "20") (name "MOTOR2B") (class "Default")
      (node (ref "U1") (pin "32") (pinfunction "PA23_32") (pintype "bidirectional"))
      (node (ref "U6") (pin "2") (pinfunction "IN2_2") (pintype "input"))
    )
    (net (code "21") (name "NEOPIXEL") (class "Default")
      (node (ref "U1") (pin "15") (pinfunction "PA10_15") (pintype "bidirectional"))
      (node (ref "U8") (pin "2") (pinfunction "I_2") (pintype "input"))
    )
    (net (code "22") (name "NEOPIXEL_INTERNAL") (class "Default")
      (node (ref "D2") (pin "2") (pinfunction "DI_2") (pintype "input"))
      (node (ref "U8") (pin "4") (pinfunction "O_4") (pintype "tri_state"))
    )
    (net (code "23") (name "NEOPIXEL_OUT") (class "Default")
      (node (ref "D2") (pin "4") (pinfunction "DO_4") (pintype "output"))
      (node (ref "J11") (pin "1") (pinfunction "1_1") (pintype "passive"))
      (node (ref "J15") (pin "2") (pinfunction "2_2") (pintype "passive"))
    )
    (net (code "24") (name "Net-(D1-Pad+)") (class "Default")
      (node (ref "D1") (pin "+") (pinfunction "+_+") (pintype "passive"))
      (node (ref "R4") (pin "1") (pinfunction "1_1") (pintype "passive"))
    )
    (net (code "25") (name "Net-(J14-Pad5)") (class "Default")
      (node (ref "J14") (pin "5") (pinfunction "5_5") (pintype "passive"))
      (node (ref "J14") (pin "6") (pinfunction "6_6") (pintype "passive"))
    )
    (net (code "26") (name "Net-(J14-Pad10)") (class "Default")
      (node (ref "J14") (pin "10") (pinfunction "10_10") (pintype "passive"))
      (node (ref "J14") (pin "9") (pinfunction "9_9") (pintype "passive"))
    )
    (net (code "27") (name "Net-(J14-Pad11)") (class "Default")
      (node (ref "J14") (pin "11") (pinfunction "11_11") (pintype "passive"))
      (node (ref "J14") (pin "12") (pinfunction "12_12") (pintype "passive"))
    )
    (net (code "28") (name "Net-(J14-Pad13)") (class "Default")
      (node (ref "J14") (pin "13") (pinfunction "13_13") (pintype "passive"))
      (node (ref "J14") (pin "14") (pinfunction "14_14") (pintype "passive"))
    )
    (net (code "29") (name "Net-(J14-Pad15)") (class "Default")
      (node (ref "J14") (pin "15") (pinfunction "15_15") (pintype "passive"))
      (node (ref "J14") (pin "16") (pinfunction "16_16") (pintype "passive"))
    )
    (net (code "30") (name "Net-(J14-Pad17)") (class "Default")
      (node (ref "J14") (pin "17") (pinfunction "17_17") (pintype "passive"))
      (node (ref "J14") (pin "18") (pinfunction "18_18") (pintype "passive"))
    )
    (net (code "31") (name "Net-(J14-Pad19)") (class "Default")
      (node (ref "J14") (pin "19") (pinfunction "19_19") (pintype "passive"))
      (node (ref "J14") (pin "20") (pinfunction "20_20") (pintype "passive"))
    )
    (net (code "32") (name "Net-(J14-Pad21)") (class "Default")
      (node (ref "J14") (pin "21") (pinfunction "21_21") (pintype "passive"))
      (node (ref "J14") (pin "22") (pinfunction "22_22") (pintype "passive"))
    )
    (net (code "33") (name "Net-(J14-Pad23)") (class "Default")
      (node (ref "J14") (pin "23") (pinfunction "23_23") (pintype "passive"))
      (node (ref "J14") (pin "24") (pinfunction "24_24") (pintype "passive"))
    )
    (net (code "34") (name "Net-(J14-Pad25)") (class "Default")
      (node (ref "J14") (pin "25") (pinfunction "25_25") (pintype "passive"))
      (node (ref "J14") (pin "26") (pinfunction "26_26") (pintype "passive"))
    )
    (net (code "35") (name "Net-(J14-Pad27)") (class "Default")
      (node (ref "J14") (pin "27") (pinfunction "27_27") (pintype "passive"))
      (node (ref "J14") (pin "28") (pinfunction "28_28") (pintype "passive"))
    )
    (net (code "36") (name "Net-(J14-Pad29)") (class "Default")
      (node (ref "J14") (pin "29") (pinfunction "29_29") (pintype "passive"))
      (node (ref "J14") (pin "30") (pinfunction "30_30") (pintype "passive"))
    )
    (net (code "37") (name "Net-(J14-Pad31)") (class "Default")
      (node (ref "J14") (pin "31") (pinfunction "31_31") (pintype "passive"))
      (node (ref "J14") (pin "32") (pinfunction "32_32") (pintype "passive"))
    )
    (net (code "38") (name "Net-(J15-Pad3)") (class "Default")
      (node (ref "J15") (pin "3") (pinfunction "3_3") (pintype "passive"))
      (node (ref "J15") (pin "4") (pinfunction "4_4") (pintype "passive"))
    )
    (net (code "39") (name "Net-(J15-Pad7)") (class "Default")
      (node (ref "J15") (pin "7") (pinfunction "7_7") (pintype "passive"))
      (node (ref "J15") (pin "8") (pinfunction "8_8") (pintype "passive"))
    )
    (net (code "40") (name "Net-(J15-Pad10)") (class "Default")
      (node (ref "J15") (pin "10") (pinfunction "10_10") (pintype "passive"))
      (node (ref "J15") (pin "9") (pinfunction "9_9") (pintype "passive"))
    )
    (net (code "41") (name "Net-(J15-Pad11)") (class "Default")
      (node (ref "J15") (pin "11") (pinfunction "11_11") (pintype "passive"))
      (node (ref "J15") (pin "12") (pinfunction "12_12") (pintype "passive"))
    )
    (net (code "42") (name "Net-(J15-Pad13)") (class "Default")
      (node (ref "J15") (pin "13") (pinfunction "13_13") (pintype "passive"))
      (node (ref "J15") (pin "14") (pinfunction "14_14") (pintype "passive"))
    )
    (net (code "43") (name "Net-(J15-Pad15)") (class "Default")
      (node (ref "J15") (pin "15") (pinfunction "15_15") (pintype "passive"))
      (node (ref "J15") (pin "16") (pinfunction "16_16") (pintype "passive"))
    )
    (net (code "44") (name "Net-(J15-Pad17)") (class "Default")
      (node (ref "J15") (pin "17") (pinfunction "17_17") (pintype "passive"))
      (node (ref "J15") (pin "18") (pinfunction "18_18") (pintype "passive"))
    )
    (net (code "45") (name "Net-(J15-Pad19)") (class "Default")
      (node (ref "J15") (pin "19") (pinfunction "19_19") (pintype "passive"))
      (node (ref "J15") (pin "20") (pinfunction "20_20") (pintype "passive"))
    )
    (net (code "46") (name "Net-(R10-Pad1)") (class "Default")
      (node (ref "R10") (pin "1") (pinfunction "1_1") (pintype "passive"))
      (node (ref "SW1") (pin "1") (pinfunction "P1_1") (pintype "passive"))
      (node (ref "SW1") (pin "4") (pinfunction "P1_4") (pintype "passive"))
    )
    (net (code "47") (name "Net-(U1-VDDANA)") (class "Default")
      (node (ref "C12") (pin "2") (pinfunction "2_2") (pintype "passive"))
      (node (ref "FB") (pin "1") (pinfunction "1_1") (pintype "passive"))
      (node (ref "U1") (pin "6") (pinfunction "VDDANA_6") (pintype "power_in"))
    )
    (net (code "48") (name "Net-(U1-VDDCORE)") (class "Default")
      (node (ref "C10") (pin "2") (pinfunction "2_2") (pintype "passive"))
      (node (ref "U1") (pin "43") (pinfunction "VDDCORE_43") (pintype "power_in"))
    )
    (net (code "49") (name "Net-(U2-BST)") (class "Default")
      (node (ref "C4") (pin "1") (pinfunction "1_1") (pintype "passive"))
      (node (ref "U2") (pin "5") (pinfunction "BST_5") (pintype "bidirectional"))
    )
    (net (code "50") (name "Net-(U2-EN{slash}SYNC)") (class "Default")
      (node (ref "R1") (pin "1") (pinfunction "1_1") (pintype "passive"))
      (node (ref "U2") (pin "6") (pinfunction "EN/SYNC_6") (pintype "bidirectional"))
    )
    (net (code "51") (name "Net-(U2-FB)") (class "Default")
      (node (ref "C5") (pin "1") (pinfunction "1_1") (pintype "passive"))
      (node (ref "R2") (pin "2") (pinfunction "2_2") (pintype "passive"))
      (node (ref "R3") (pin "1") (pinfunction "1_1") (pintype "passive"))
      (node (ref "U2") (pin "8") (pinfunction "FB_8") (pintype "bidirectional"))
    )
    (net (code "52") (name "Net-(U2-SW)") (class "Default")
      (node (ref "C4") (pin "2") (pinfunction "2_2") (pintype "passive"))
      (node (ref "L1") (pin "1") (pinfunction "1_1") (pintype "passive"))
      (node (ref "U2") (pin "3") (pinfunction "SW_3") (pintype "bidirectional"))
    )
    (net (code "53") (name "Net-(U2-VCC)") (class "Default")
      (node (ref "C3") (pin "2") (pinfunction "2_2") (pintype "passive"))
      (node (ref "U2") (pin "7") (pinfunction "VCC_7") (pintype "bidirectional"))
    )
    (net (code "54") (name "Net-(U5-ILIM)") (class "Default")
      (node (ref "R7") (pin "1") (pinfunction "1_1") (pintype "passive"))
      (node (ref "U5") (pin "4") (pinfunction "ILIM_4") (pintype "input"))
    )
    (net (code "55") (name "Net-(U5-OUT1)") (class "Default")
      (node (ref "J2") (pin "1") (pinfunction "1_1") (pintype "passive"))
      (node (ref "U5") (pin "6") (pinfunction "OUT1_6") (pintype "output"))
    )
    (net (code "56") (name "Net-(U5-OUT2)") (class "Default")
      (node (ref "J2") (pin "2") (pinfunction "2_2") (pintype "passive"))
      (node (ref "U5") (pin "8") (pinfunction "OUT2_8") (pintype "output"))
    )
    (net (code "57") (name "Net-(U6-ILIM)") (class "Default")
      (node (ref "R8") (pin "1") (pinfunction "1_1") (pintype "passive"))
      (node (ref "U6") (pin "4") (pinfunction "ILIM_4") (pintype "input"))
    )
    (net (code "58") (name "Net-(U6-OUT1)") (class "Default")
      (node (ref "J3") (pin "1") (pinfunction "1_1") (pintype "passive"))
      (node (ref "U6") (pin "6") (pinfunction "OUT1_6") (pintype "output"))
    )
    (net (code "59") (name "Net-(U6-OUT2)") (class "Default")
      (node (ref "J3") (pin "2") (pinfunction "2_2") (pintype "passive"))
      (node (ref "U6") (pin "8") (pinfunction "OUT2_8") (pintype "output"))
    )
    (net (code "60") (name "Net-(U7-B2)") (class "Default")
      (node (ref "J8") (pin "1") (pinfunction "1_1") (pintype "passive"))
      (node (ref "U7") (pin "12") (pinfunction "B2_12") (pintype "bidirectional"))
    )
    (net (code "61") (name "Net-(U7-B3)") (class "Default")
      (node (ref "J9") (pin "1") (pinfunction "1_1") (pintype "passive"))
      (node (ref "U7") (pin "11") (pinfunction "B3_11") (pintype "bidirectional"))
    )
    (net (code "62") (name "Net-(U7-B4)") (class "Default")
      (node (ref "J10") (pin "1") (pinfunction "1_1") (pintype "passive"))
      (node (ref "U7") (pin "10") (pinfunction "B4_10") (pintype "bidirectional"))
    )
    (net (code "63") (name "RX") (class "Default")
      (node (ref "J17") (pin "P$3") (pinfunction "3_P$3") (pintype "passive"))
      (node (ref "U1") (pin "20") (pinfunction "PB11_20") (pintype "bidirectional"))
    )
    (net (code "64") (name "SCL1") (class "Default")
      (node (ref "J15") (pin "21") (pinfunction "21_21") (pintype "passive"))
      (node (ref "J15") (pin "22") (pinfunction "22_22") (pintype "passive"))
      (node (ref "J6") (pin "1") (pinfunction "1_1") (pintype "passive"))
      (node (ref "R13") (pin "2") (pinfunction "2_2") (pintype "passive"))
      (node (ref "U1") (pin "26") (pinfunction "PA17_26") (pintype "bidirectional"))
    )
    (net (code "65") (name "SCL2") (class "Default")
      (node (ref "J16") (pin "P$2") (pinfunction "2_P$2") (pintype "passive"))
      (node (ref "R15") (pin "2") (pinfunction "2_2") (pintype "passive"))
      (node (ref "U1") (pin "22") (pinfunction "PA13_22") (pintype "bidirectional"))
      (node (ref "U9") (pin "13") (pinfunction "AP_SCL/AP_SCLK_13") (pintype "input"))
    )
    (net (code "66") (name "SDA1") (class "Default")
      (node (ref "J15") (pin "23") (pinfunction "23_23") (pintype "passive"))
      (node (ref "J15") (pin "24") (pinfunction "24_24") (pintype "passive"))
      (node (ref "J6") (pin "2") (pinfunction "2_2") (pintype "passive"))
      (node (ref "R14") (pin "2") (pinfunction "2_2") (pintype "passive"))
      (node (ref "U1") (pin "25") (pinfunction "PA16_25") (pintype "bidirectional"))
    )
    (net (code "67") (name "SDA2") (class "Default")
      (node (ref "J16") (pin "P$3") (pinfunction "3_P$3") (pintype "passive"))
      (node (ref "R16") (pin "2") (pinfunction "2_2") (pintype "passive"))
      (node (ref "U1") (pin "21") (pinfunction "PA12_21") (pintype "bidirectional"))
      (node (ref "U9") (pin "14") (pinfunction "AP_SDA/AP_SDIO/AP_SDI_14") (pintype "bidirectional"))
    )
    (net (code "68") (name "SERVO1") (class "Default")
      (node (ref "J12") (pin "3") (pinfunction "3_3") (pintype "passive"))
      (node (ref "U1") (pin "1") (pinfunction "PA00_1") (pintype "bidirectional"))
    )
    (net (code "69") (name "SERVO2") (class "Default")
      (node (ref "J12") (pin "6") (pinfunction "6_6") (pintype "passive"))
      (node (ref "U1") (pin "2") (pinfunction "PA01_2") (pintype "bidirectional"))
    )
    (net (code "70") (name "SERVO3") (class "Default")
      (node (ref "J12") (pin "9") (pinfunction "9_9") (pintype "passive"))
      (node (ref "U1") (pin "13") (pinfunction "PA08_13") (pintype "bidirectional"))
    )
    (net (code "71") (name "SERVO4") (class "Default")
      (node (ref "J12") (pin "12") (pinfunction "12_12") (pintype "passive"))
      (node (ref "U1") (pin "14") (pinfunction "PA09_14") (pintype "bidirectional"))
    )
    (net (code "72") (name "SONAR1ECHO") (class "Default")
      (node (ref "U1") (pin "41") (pinfunction "PA28_41") (pintype "bidirectional"))
      (node (ref "U7") (pin "5") (pinfunction "A4_5") (pintype "bidirectional"))
    )
    (net (code "73") (name "SONAR1TRIG") (class "Default")
      (node (ref "J10") (pin "2") (pinfunction "2_2") (pintype "passive"))
      (node (ref "U1") (pin "39") (pinfunction "PA27_39") (pintype "bidirectional"))
    )
    (net (code "74") (name "SONAR2ECHO") (class "Default")
      (node (ref "U1") (pin "47") (pinfunction "PB02_47") (pintype "bidirectional"))
      (node (ref "U7") (pin "4") (pinfunction "A3_4") (pintype "bidirectional"))
    )
    (net (code "75") (name "SONAR2TRIG") (class "Default")
      (node (ref "J9") (pin "2") (pinfunction "2_2") (pintype "passive"))
      (node (ref "U1") (pin "38") (pinfunction "PB23_38") (pintype "bidirectional"))
    )
    (net (code "76") (name "SONAR3ECHO") (class "Default")
      (node (ref "U1") (pin "48") (pinfunction "PB03_48") (pintype "bidirectional"))
      (node (ref "U7") (pin "3") (pinfunction "A2_3") (pintype "bidirectional"))
    )
    (net (code "77") (name "SONAR3TRIG") (class "Default")
      (node (ref "J8") (pin "2") (pinfunction "2_2") (pintype "passive"))
      (node (ref "U1") (pin "37") (pinfunction "PB22_37") (pintype "bidirectional"))
    )
    (net (code "78") (name "SWCLK") (class "Default")
      (node (ref "R11") (pin "2") (pinfunction "2_2") (pintype "passive"))
      (node (ref "TP2") (pin "TP") (pinfunction "TP_TP") (pintype "input"))
      (node (ref "U1") (pin "45") (pinfunction "PA30_45") (pintype "bidirectional"))
    )
    (net (code "79") (name "SWDIO") (class "Default")
      (node (ref "TP3") (pin "TP") (pinfunction "TP_TP") (pintype "input"))
      (node (ref "U1") (pin "46") (pinfunction "PA31_46") (pintype "bidirectional"))
    )
    (net (code "80") (name "TX") (class "Default")
      (node (ref "J17") (pin "P$2") (pinfunction "2_P$2") (pintype "passive"))
      (node (ref "U1") (pin "19") (pinfunction "PB10_19") (pintype "bidirectional"))
    )
    (net (code "81") (name "VSENSE") (class "Default")
      (node (ref "R5") (pin "1") (pinfunction "1_1") (pintype "passive"))
      (node (ref "R6") (pin "1") (pinfunction "1_1") (pintype "passive"))
      (node (ref "U1") (pin "12") (pinfunction "PA07_12") (pintype "bidirectional"))
    )
    (net (code "82") (name "unconnected-(J15-Pad1)") (class "Default")
      (node (ref "J15") (pin "1") (pinfunction "1_1") (pintype "passive"))
    )
    (net (code "83") (name "unconnected-(J15-Pad5)") (class "Default")
      (node (ref "J15") (pin "5") (pinfunction "5_5") (pintype "passive"))
    )
    (net (code "84") (name "unconnected-(J17-4-PadP$4)") (class "Default")
      (node (ref "J17") (pin "P$4") (pinfunction "4_P$4") (pintype "passive"))
    )
    (net (code "85") (name "unconnected-(J17-5-PadP$5)") (class "Default")
      (node (ref "J17") (pin "P$5") (pinfunction "5_P$5") (pintype "passive"))
    )
    (net (code "86") (name "unconnected-(U1-PA03-Pad4)") (class "Default")
      (node (ref "U1") (pin "4") (pinfunction "PA03_4") (pintype "bidirectional"))
    )
    (net (code "87") (name "unconnected-(U1-PA11-Pad16)") (class "Default")
      (node (ref "U1") (pin "16") (pinfunction "PA11_16") (pintype "bidirectional"))
    )
    (net (code "88") (name "unconnected-(U7-A1-Pad2)") (class "Default")
      (node (ref "U7") (pin "2") (pinfunction "A1_2") (pintype "bidirectional"))
    )
    (net (code "89") (name "unconnected-(U7-B1-Pad13)") (class "Default")
      (node (ref "U7") (pin "13") (pinfunction "B1_13") (pintype "bidirectional"))
    )
    (net (code "90") (name "unconnected-(U7-NC-Pad9)") (class "Default")
      (node (ref "U7") (pin "9") (pinfunction "NC_9") (pintype "no_connect"))
    )
    (net (code "91") (name "unconnected-(U7-NC_2-Pad6)") (class "Default")
      (node (ref "U7") (pin "6") (pinfunction "NC_2_6") (pintype "no_connect"))
    )
    (net (code "92") (name "unconnected-(U9-INT1{slash}INT-Pad4)") (class "Default")
      (node (ref "U9") (pin "4") (pinfunction "INT1/INT_4") (pintype "output"))
    )
    (net (code "93") (name "unconnected-(U9-RESV_1-Pad2)") (class "Default")
      (node (ref "U9") (pin "2") (pinfunction "RESV_1_2") (pintype "bidirectional"))
    )
    (net (code "94") (name "unconnected-(U9-RESV_2-Pad3)") (class "Default")
      (node (ref "U9") (pin "3") (pinfunction "RESV_2_3") (pintype "bidirectional"))
    )
    (net (code "95") (name "unconnected-(U9-RESV_4-Pad10)") (class "Default")
      (node (ref "U9") (pin "10") (pinfunction "RESV_4_10") (pintype "bidirectional"))
    )
    (net (code "96") (name "unconnected-(U9-RESV_5-Pad11)") (class "Default")
      (node (ref "U9") (pin "11") (pinfunction "RESV_5_11") (pintype "bidirectional"))
    )
    (net (code "97") (name "unconnected-(USB1-ID-Pad4)") (class "Default")
      (node (ref "USB1") (pin "4") (pinfunction "ID_4") (pintype "bidirectional"))
    )
    (net (code "98") (name "unconnected-(USB1-VCC-Pad1)") (class "Default")
      (node (ref "USB1") (pin "1") (pinfunction "VCC_1") (pintype "bidirectional"))
    )
    (net (code "99") (name "~{RESET}") (class "Default")
      (node (ref "C14") (pin "1") (pinfunction "1_1") (pintype "passive"))
      (node (ref "J14") (pin "1") (pinfunction "1_1") (pintype "passive"))
      (node (ref "J14") (pin "2") (pinfunction "2_2") (pintype "passive"))
      (node (ref "R10") (pin "2") (pinfunction "2_2") (pintype "passive"))
      (node (ref "TP1") (pin "TP") (pinfunction "TP_TP") (pintype "input"))
      (node (ref "U1") (pin "40") (pinfunction "RSTN_40") (pintype "bidirectional"))
    )
  )
)
